# MySens-GWeasySensRS485-003.net
KiCad netlist of a schematic drawn in EAGLE
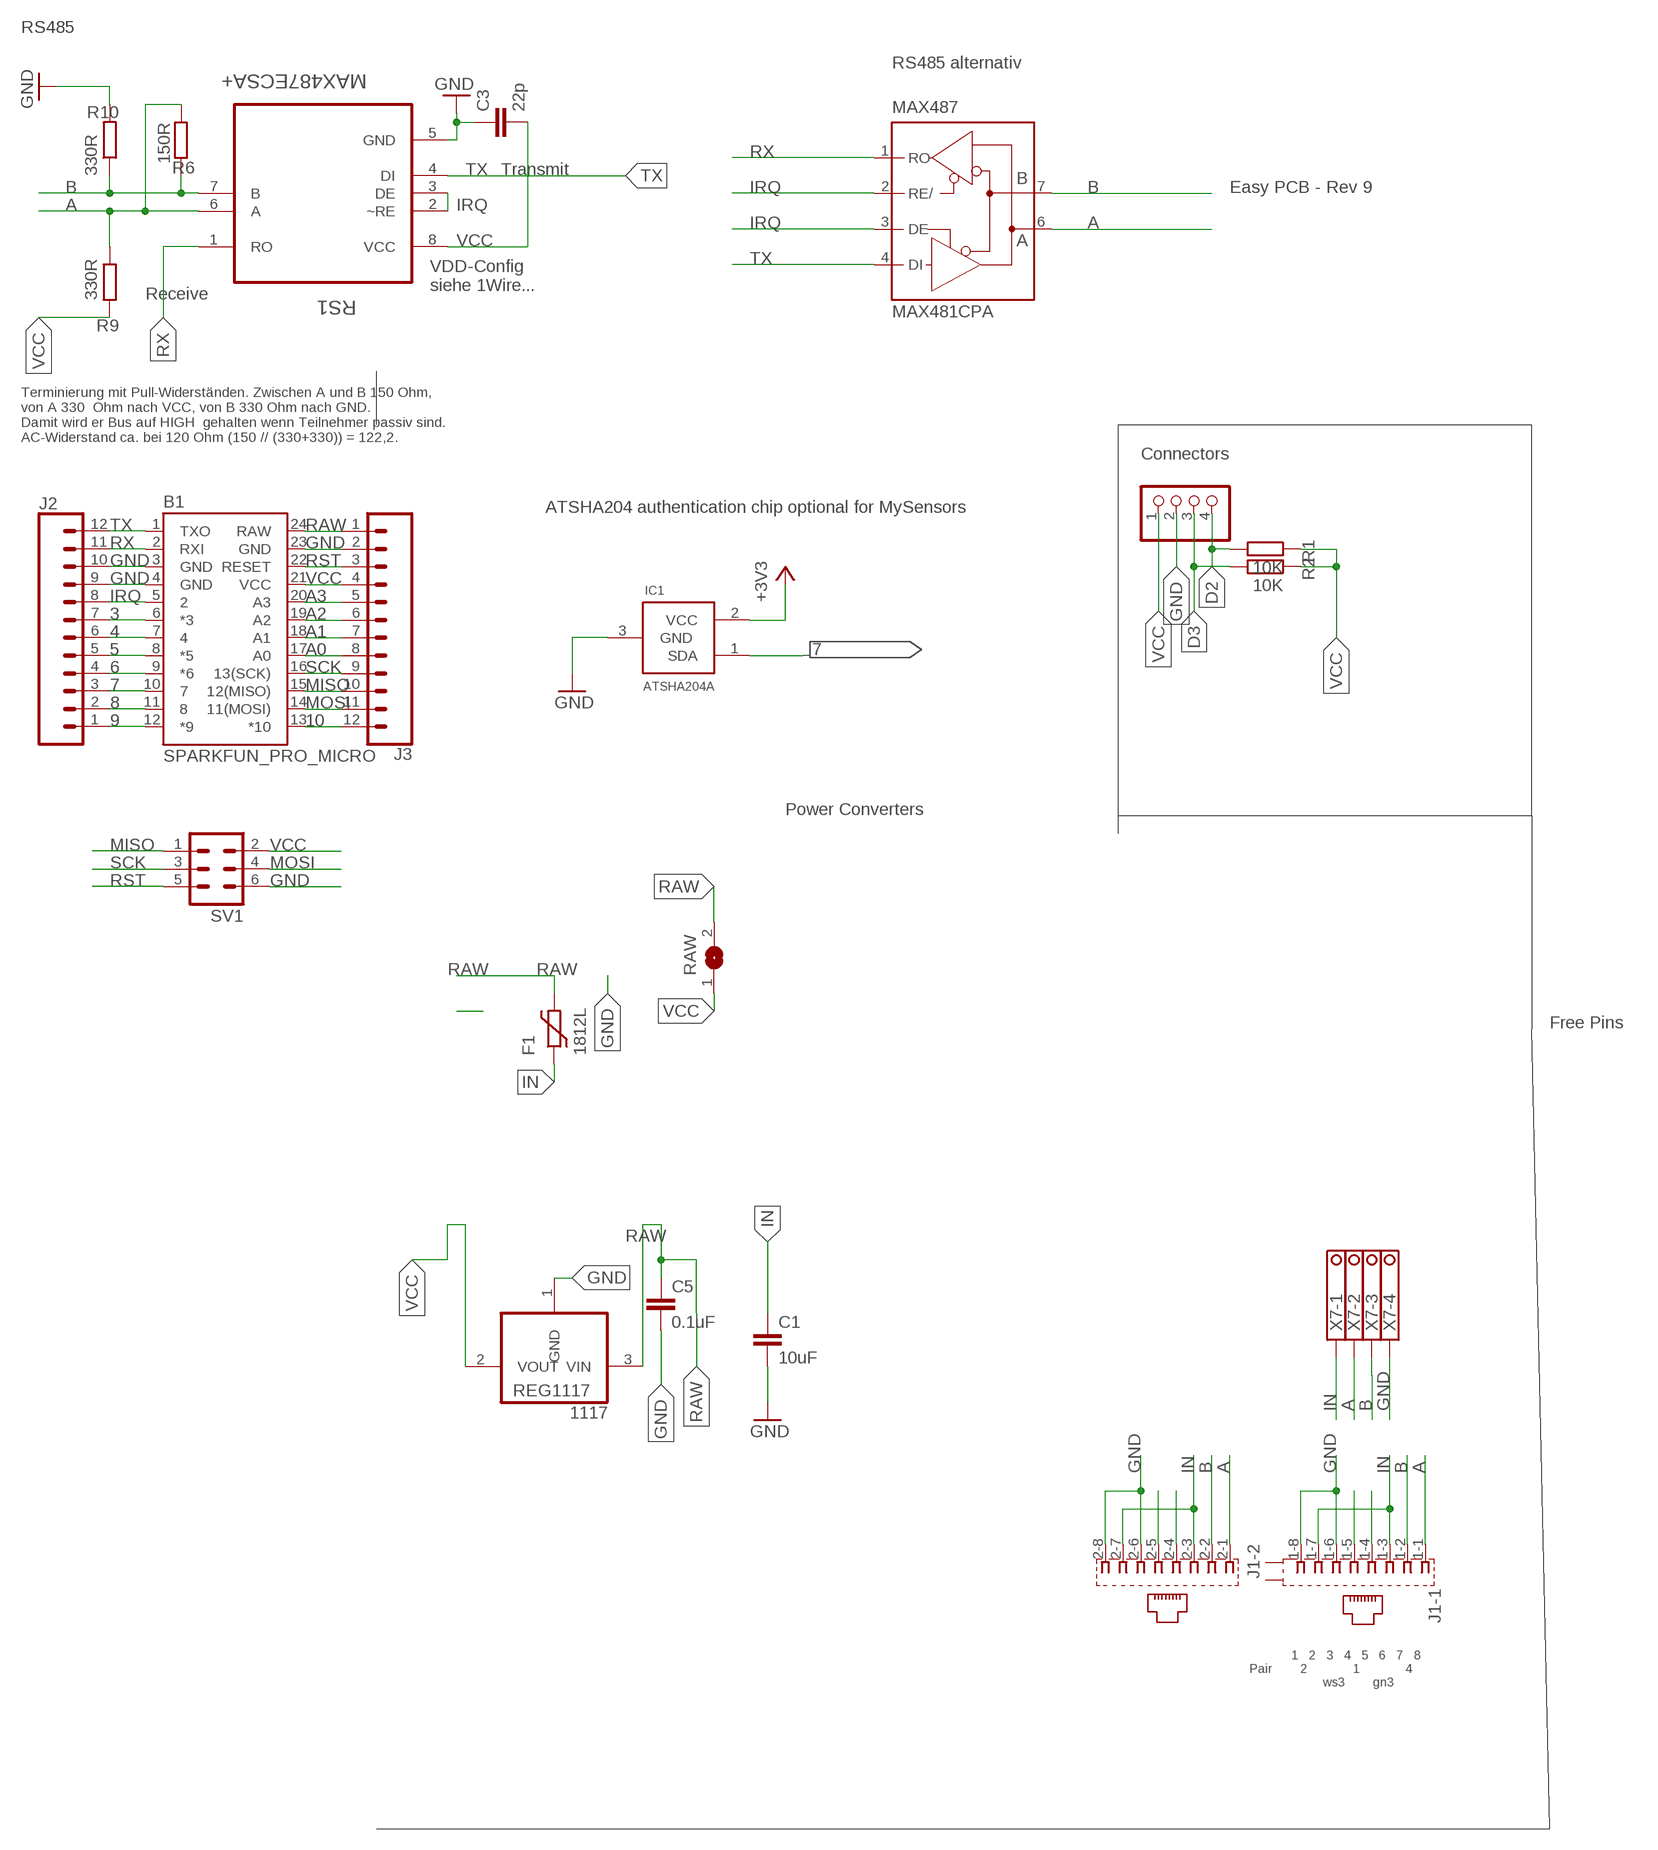
[diagram p0: schematic, sheet 1]

(export (version "E")
  (design (tool "Eeschema 10.0.6"))
  (components
    (comp (ref "1117")
      (value "REG1117")
      (footprint "eagle-import:SOT223")
      (libsource (lib "eagle-import") (part "REG1117"))
    )
    (comp (ref "B1")
      (value "SPARKFUN_PRO_MICRO")
      (footprint "eagle-import:SPARKFUN_PRO_MICRO")
      (libsource (lib "eagle-import") (part "SPARKFUN_PRO_MICRO"))
    )
    (comp (ref "C1")
      (value "10uF")
      (footprint "eagle-import:0805")
      (libsource (lib "eagle-import") (part "CAP0805"))
    )
    (comp (ref "C3")
      (value "22p")
      (footprint "eagle-import:C0805")
      (libsource (lib "eagle-import") (part "C-EUC0805"))
    )
    (comp (ref "C5")
      (value "0.1uF")
      (footprint "eagle-import:C1206")
      (libsource (lib "eagle-import") (part "C-EUC1206"))
    )
    (comp (ref "F1")
      (value "1812L")
      (footprint "eagle-import:1812L")
      (libsource (lib "eagle-import") (part "1812L"))
    )
    (comp (ref "IC1")
      (value "ATSHA204A")
      (footprint "eagle-import:SOT23")
      (libsource (lib "eagle-import") (part "ATSHA204A"))
    )
    (comp (ref "J1")
      (value "557570-1")
      (footprint "eagle-import:557570-1")
      (libsource (lib "eagle-import") (part "557570-1"))
    )
    (comp (ref "J2")
      (value "CONN_12")
      (footprint "eagle-import:1X12")
      (libsource (lib "eagle-import") (part "CONN_12"))
    )
    (comp (ref "J3")
      (value "CONN_12")
      (footprint "eagle-import:1X12")
      (libsource (lib "eagle-import") (part "CONN_12"))
    )
    (comp (ref "JP10")
      (value "PINHD-1X04_2.54-S")
      (footprint "eagle-import:1X04-S")
      (libsource (lib "eagle-import") (part "PINHD-1X04_2.54-S"))
    )
    (comp (ref "MAX487")
      (value "MAX481CPA")
      (footprint "eagle-import:DIL08")
      (libsource (lib "eagle-import") (part "MAX481CPA"))
    )
    (comp (ref "R1")
      (value "10K")
      (footprint "eagle-import:R0805")
      (libsource (lib "eagle-import") (part "R-EU_R0805"))
    )
    (comp (ref "R2")
      (value "10K")
      (footprint "eagle-import:R0805")
      (libsource (lib "eagle-import") (part "R-EU_R0805"))
    )
    (comp (ref "R6")
      (value "150R")
      (footprint "eagle-import:R0805")
      (libsource (lib "eagle-import") (part "R-EU_R0805"))
    )
    (comp (ref "R9")
      (value "330R")
      (footprint "eagle-import:R0805")
      (libsource (lib "eagle-import") (part "R-EU_R0805"))
    )
    (comp (ref "R10")
      (value "330R")
      (footprint "eagle-import:R0805")
      (libsource (lib "eagle-import") (part "R-EU_R0805"))
    )
    (comp (ref "RAW") (value "SJ") (footprint "eagle-import:SJ") (libsource (lib "eagle-import") (part "SJ")))
    (comp (ref "RS1")
      (value "MAX487ECSA+")
      (footprint "eagle-import:SOIC127P600X175-8N")
      (libsource (lib "eagle-import") (part "MAX487ECSA+"))
    )
    (comp (ref "SV1")
      (value "MA03-2")
      (footprint "eagle-import:MA03-2")
      (libsource (lib "eagle-import") (part "MA03-2"))
    )
    (comp (ref "X7")
      (value "1751264")
      (footprint "eagle-import:1751264")
      (libsource (lib "eagle-import") (part "1751264"))
    )
  )
  (nets
    (net (code "1") (name "+3V3") (class "Default")
      (node (ref "IC1") (pin "2") (pinfunction "VCC_2") (pintype "bidirectional"))
    )
    (net (code "2") (name "/3") (class "Default")
      (node (ref "B1") (pin "6") (pinfunction "*3_6") (pintype "bidirectional"))
      (node (ref "J2") (pin "7") (pinfunction "7_7") (pintype "passive"))
    )
    (net (code "3") (name "/4") (class "Default")
      (node (ref "B1") (pin "7") (pinfunction "4_7") (pintype "bidirectional"))
      (node (ref "J2") (pin "6") (pinfunction "6_6") (pintype "passive"))
    )
    (net (code "4") (name "/5") (class "Default")
      (node (ref "B1") (pin "8") (pinfunction "*5_8") (pintype "bidirectional"))
      (node (ref "J2") (pin "5") (pinfunction "5_5") (pintype "passive"))
    )
    (net (code "5") (name "/6") (class "Default")
      (node (ref "B1") (pin "9") (pinfunction "*6_9") (pintype "bidirectional"))
      (node (ref "J2") (pin "4") (pinfunction "4_4") (pintype "passive"))
    )
    (net (code "6") (name "/7") (class "Default")
      (node (ref "B1") (pin "10") (pinfunction "7_10") (pintype "bidirectional"))
      (node (ref "IC1") (pin "1") (pinfunction "SDA_1") (pintype "bidirectional"))
      (node (ref "J2") (pin "3") (pinfunction "3_3") (pintype "passive"))
    )
    (net (code "7") (name "/8") (class "Default")
      (node (ref "B1") (pin "11") (pinfunction "8_11") (pintype "bidirectional"))
      (node (ref "J2") (pin "2") (pinfunction "2_2") (pintype "passive"))
    )
    (net (code "8") (name "/9") (class "Default")
      (node (ref "B1") (pin "12") (pinfunction "*9_12") (pintype "bidirectional"))
      (node (ref "J2") (pin "1") (pinfunction "1_1") (pintype "passive"))
    )
    (net (code "9") (name "/10") (class "Default")
      (node (ref "B1") (pin "13") (pinfunction "*10_13") (pintype "bidirectional"))
      (node (ref "J3") (pin "12") (pinfunction "12_12") (pintype "passive"))
    )
    (net (code "10") (name "/A") (class "Default")
      (node (ref "J1") (pin "1-1") (pinfunction "1_1-1") (pintype "passive"))
      (node (ref "J1") (pin "2-1") (pinfunction "1_2-1") (pintype "passive"))
      (node (ref "MAX487") (pin "6") (pinfunction "A_6") (pintype "passive"))
      (node (ref "R6") (pin "1") (pinfunction "1_1") (pintype "passive"))
      (node (ref "R9") (pin "2") (pinfunction "2_2") (pintype "passive"))
      (node (ref "RS1") (pin "6") (pinfunction "A_6") (pintype "bidirectional"))
      (node (ref "X7") (pin "2") (pinfunction "K_2") (pintype "passive"))
    )
    (net (code "11") (name "/A0") (class "Default")
      (node (ref "B1") (pin "17") (pinfunction "A0_17") (pintype "bidirectional"))
      (node (ref "J3") (pin "8") (pinfunction "8_8") (pintype "passive"))
    )
    (net (code "12") (name "/A1") (class "Default")
      (node (ref "B1") (pin "18") (pinfunction "A1_18") (pintype "bidirectional"))
      (node (ref "J3") (pin "7") (pinfunction "7_7") (pintype "passive"))
    )
    (net (code "13") (name "/A2") (class "Default")
      (node (ref "B1") (pin "19") (pinfunction "A2_19") (pintype "bidirectional"))
      (node (ref "J3") (pin "6") (pinfunction "6_6") (pintype "passive"))
    )
    (net (code "14") (name "/A3") (class "Default")
      (node (ref "B1") (pin "20") (pinfunction "A3_20") (pintype "bidirectional"))
      (node (ref "J3") (pin "5") (pinfunction "5_5") (pintype "passive"))
    )
    (net (code "15") (name "/B") (class "Default")
      (node (ref "J1") (pin "1-2") (pinfunction "2_1-2") (pintype "passive"))
      (node (ref "J1") (pin "2-2") (pinfunction "2_2-2") (pintype "passive"))
      (node (ref "MAX487") (pin "7") (pinfunction "B_7") (pintype "passive"))
      (node (ref "R10") (pin "1") (pinfunction "1_1") (pintype "passive"))
      (node (ref "R6") (pin "2") (pinfunction "2_2") (pintype "passive"))
      (node (ref "RS1") (pin "7") (pinfunction "B_7") (pintype "bidirectional"))
      (node (ref "X7") (pin "3") (pinfunction "K_3") (pintype "passive"))
    )
    (net (code "16") (name "/IRQ") (class "Default")
      (node (ref "B1") (pin "5") (pinfunction "2_5") (pintype "bidirectional"))
      (node (ref "J2") (pin "8") (pinfunction "8_8") (pintype "passive"))
      (node (ref "MAX487") (pin "2") (pinfunction "RE/_2") (pintype "input"))
      (node (ref "MAX487") (pin "3") (pinfunction "DE_3") (pintype "input"))
      (node (ref "RS1") (pin "2") (pinfunction "~{RE}_2") (pintype "input"))
      (node (ref "RS1") (pin "3") (pinfunction "DE_3") (pintype "input"))
    )
    (net (code "17") (name "/MISO") (class "Default")
      (node (ref "B1") (pin "15") (pinfunction "12(MISO)_15") (pintype "bidirectional"))
      (node (ref "J3") (pin "10") (pinfunction "10_10") (pintype "passive"))
      (node (ref "SV1") (pin "1") (pinfunction "1_1") (pintype "passive"))
    )
    (net (code "18") (name "/MOSI") (class "Default")
      (node (ref "B1") (pin "14") (pinfunction "11(MOSI)_14") (pintype "bidirectional"))
      (node (ref "J3") (pin "11") (pinfunction "11_11") (pintype "passive"))
      (node (ref "SV1") (pin "4") (pinfunction "4_4") (pintype "passive"))
    )
    (net (code "19") (name "/RST") (class "Default")
      (node (ref "B1") (pin "22") (pinfunction "RESET_22") (pintype "bidirectional"))
      (node (ref "J3") (pin "3") (pinfunction "3_3") (pintype "passive"))
      (node (ref "SV1") (pin "5") (pinfunction "5_5") (pintype "passive"))
    )
    (net (code "20") (name "/SCK") (class "Default")
      (node (ref "B1") (pin "16") (pinfunction "13(SCK)_16") (pintype "bidirectional"))
      (node (ref "J3") (pin "9") (pinfunction "9_9") (pintype "passive"))
      (node (ref "SV1") (pin "3") (pinfunction "3_3") (pintype "passive"))
    )
    (net (code "21") (name "D2") (class "Default")
      (node (ref "JP10") (pin "4") (pinfunction "4_4") (pintype "passive"))
      (node (ref "R1") (pin "2") (pinfunction "2_2") (pintype "passive"))
    )
    (net (code "22") (name "D3") (class "Default")
      (node (ref "JP10") (pin "3") (pinfunction "3_3") (pintype "passive"))
      (node (ref "R2") (pin "2") (pinfunction "2_2") (pintype "passive"))
    )
    (net (code "23") (name "GND") (class "Default")
      (node (ref "1117") (pin "1") (pinfunction "GND_1") (pintype "power_in"))
      (node (ref "B1") (pin "23") (pinfunction "GND_23") (pintype "power_in"))
      (node (ref "B1") (pin "3") (pinfunction "GND_3") (pintype "power_in"))
      (node (ref "B1") (pin "4") (pinfunction "GND_4") (pintype "power_in"))
      (node (ref "C1") (pin "2") (pinfunction "2_2") (pintype "passive"))
      (node (ref "C3") (pin "1") (pinfunction "1_1") (pintype "passive"))
      (node (ref "C5") (pin "2") (pinfunction "2_2") (pintype "passive"))
      (node (ref "IC1") (pin "3") (pinfunction "GND_3") (pintype "bidirectional"))
      (node (ref "J1") (pin "1-6") (pinfunction "6_1-6") (pintype "passive"))
      (node (ref "J1") (pin "1-8") (pinfunction "8_1-8") (pintype "passive"))
      (node (ref "J1") (pin "2-6") (pinfunction "6_2-6") (pintype "passive"))
      (node (ref "J1") (pin "2-8") (pinfunction "8_2-8") (pintype "passive"))
      (node (ref "J2") (pin "10") (pinfunction "10_10") (pintype "passive"))
      (node (ref "J2") (pin "9") (pinfunction "9_9") (pintype "passive"))
      (node (ref "J3") (pin "2") (pinfunction "2_2") (pintype "passive"))
      (node (ref "JP10") (pin "2") (pinfunction "2_2") (pintype "passive"))
      (node (ref "R10") (pin "2") (pinfunction "2_2") (pintype "passive"))
      (node (ref "RS1") (pin "5") (pinfunction "GND_5") (pintype "passive"))
      (node (ref "SV1") (pin "6") (pinfunction "6_6") (pintype "passive"))
      (node (ref "X7") (pin "4") (pinfunction "K_4") (pintype "passive"))
    )
    (net (code "24") (name "IN") (class "Default")
      (node (ref "C1") (pin "1") (pinfunction "1_1") (pintype "passive"))
      (node (ref "F1") (pin "P$1") (pinfunction "1_P$1") (pintype "passive"))
      (node (ref "J1") (pin "1-3") (pinfunction "3_1-3") (pintype "passive"))
      (node (ref "J1") (pin "1-7") (pinfunction "7_1-7") (pintype "passive"))
      (node (ref "J1") (pin "2-3") (pinfunction "3_2-3") (pintype "passive"))
      (node (ref "J1") (pin "2-7") (pinfunction "7_2-7") (pintype "passive"))
      (node (ref "X7") (pin "1") (pinfunction "K_1") (pintype "passive"))
    )
    (net (code "25") (name "RAW") (class "Default")
      (node (ref "1117") (pin "3") (pinfunction "VIN_3") (pintype "input"))
      (node (ref "B1") (pin "24") (pinfunction "RAW_24") (pintype "power_in"))
      (node (ref "C5") (pin "1") (pinfunction "1_1") (pintype "passive"))
      (node (ref "F1") (pin "P$2") (pinfunction "2_P$2") (pintype "passive"))
      (node (ref "J3") (pin "1") (pinfunction "1_1") (pintype "passive"))
      (node (ref "RAW") (pin "2") (pinfunction "2_2") (pintype "passive"))
    )
    (net (code "26") (name "RX") (class "Default")
      (node (ref "B1") (pin "2") (pinfunction "RXI_2") (pintype "bidirectional"))
      (node (ref "J2") (pin "11") (pinfunction "11_11") (pintype "passive"))
      (node (ref "MAX487") (pin "1") (pinfunction "RO_1") (pintype "output"))
      (node (ref "RS1") (pin "1") (pinfunction "RO_1") (pintype "output"))
    )
    (net (code "27") (name "TX") (class "Default")
      (node (ref "B1") (pin "1") (pinfunction "TXO_1") (pintype "bidirectional"))
      (node (ref "J2") (pin "12") (pinfunction "12_12") (pintype "passive"))
      (node (ref "MAX487") (pin "4") (pinfunction "DI_4") (pintype "input"))
      (node (ref "RS1") (pin "4") (pinfunction "DI_4") (pintype "input"))
    )
    (net (code "28") (name "VCC") (class "Default")
      (node (ref "1117") (pin "2") (pinfunction "VOUT_2") (pintype "output"))
      (node (ref "B1") (pin "21") (pinfunction "VCC_21") (pintype "power_in"))
      (node (ref "C3") (pin "2") (pinfunction "2_2") (pintype "passive"))
      (node (ref "J3") (pin "4") (pinfunction "4_4") (pintype "passive"))
      (node (ref "JP10") (pin "1") (pinfunction "1_1") (pintype "passive"))
      (node (ref "R1") (pin "1") (pinfunction "1_1") (pintype "passive"))
      (node (ref "R2") (pin "1") (pinfunction "1_1") (pintype "passive"))
      (node (ref "R9") (pin "1") (pinfunction "1_1") (pintype "passive"))
      (node (ref "RAW") (pin "1") (pinfunction "1_1") (pintype "passive"))
      (node (ref "RS1") (pin "8") (pinfunction "VCC_8") (pintype "power_in"))
      (node (ref "SV1") (pin "2") (pinfunction "2_2") (pintype "passive"))
    )
    (net (code "29") (name "unconnected-(J1A-4-Pad1-4)") (class "Default")
      (node (ref "J1") (pin "1-4") (pinfunction "4_1-4") (pintype "passive"))
    )
    (net (code "30") (name "unconnected-(J1A-5-Pad1-5)") (class "Default")
      (node (ref "J1") (pin "1-5") (pinfunction "5_1-5") (pintype "passive"))
    )
    (net (code "31") (name "unconnected-(J1A-S1-PadG3)") (class "Default")
      (node (ref "J1") (pin "G3") (pinfunction "S1_G3") (pintype "passive"))
    )
    (net (code "32") (name "unconnected-(J1A-S2-PadG1)") (class "Default")
      (node (ref "J1") (pin "G1") (pinfunction "S2_G1") (pintype "passive"))
    )
    (net (code "33") (name "unconnected-(J1B-4-Pad2-4)") (class "Default")
      (node (ref "J1") (pin "2-4") (pinfunction "4_2-4") (pintype "passive"))
    )
    (net (code "34") (name "unconnected-(J1B-5-Pad2-5)") (class "Default")
      (node (ref "J1") (pin "2-5") (pinfunction "5_2-5") (pintype "passive"))
    )
  )
)
